# main.net
KiCad netlist of a schematic drawn in Altium Designer
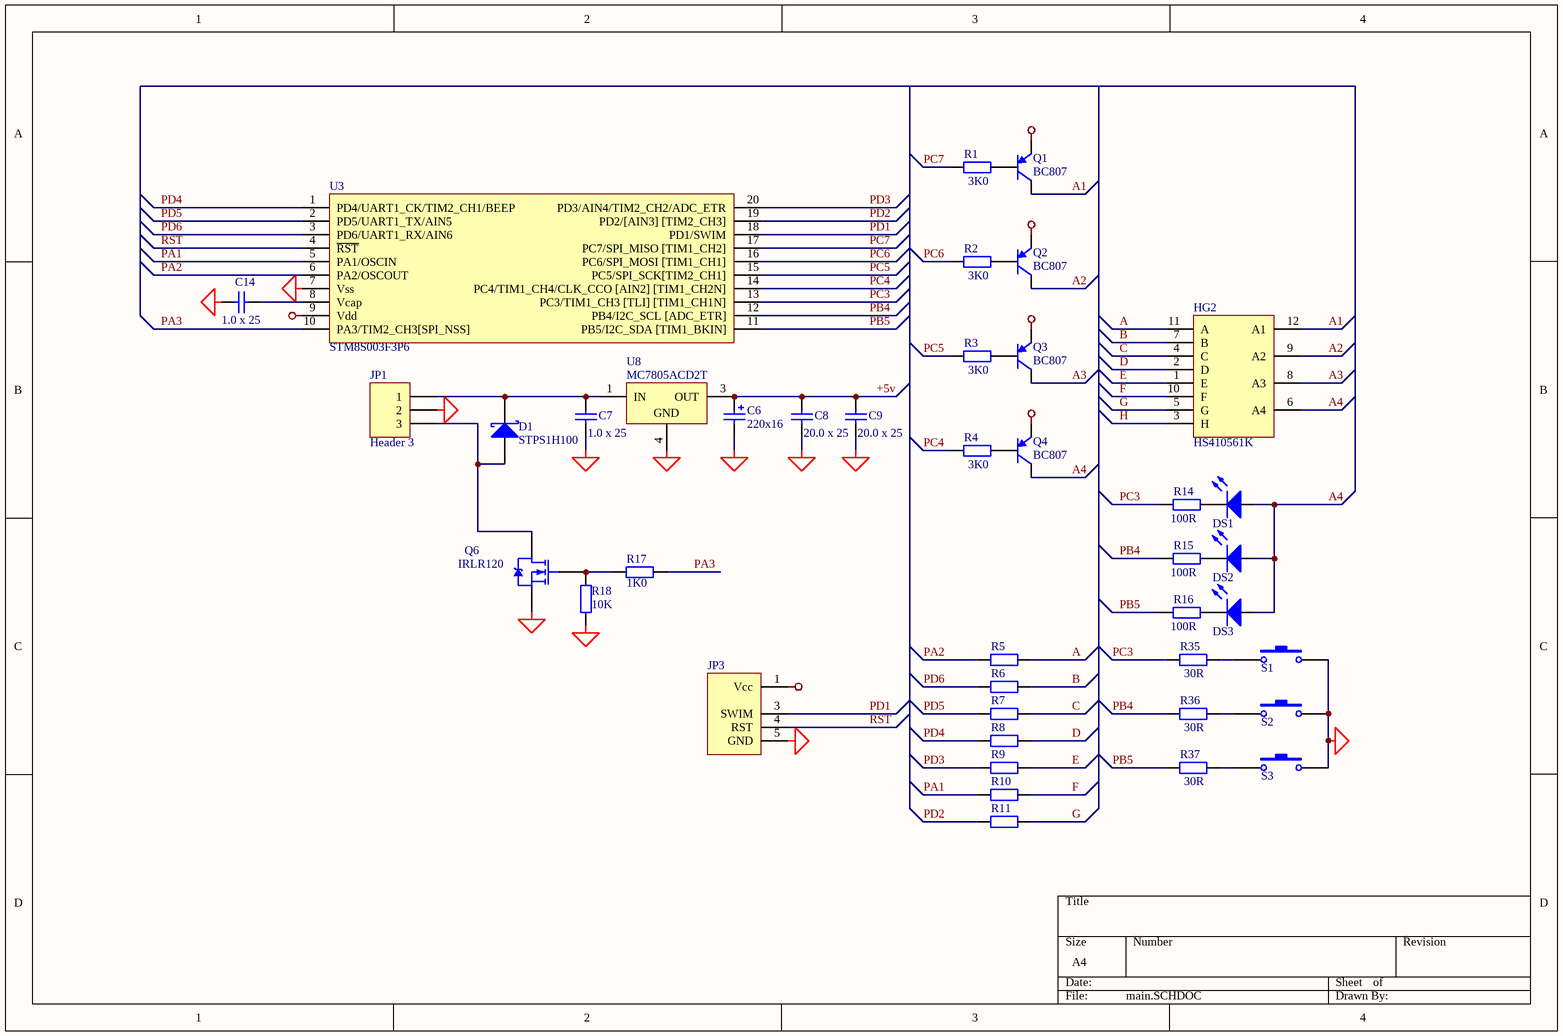
[diagram p0: main.SCHDOC]

(export (version "E")
  (design (tool "Eeschema 10.0.6"))
  (components
    (comp (ref "C6")
      (value "220x16")
      (footprint "el3")
      (description "Polarized Capacitor (Radial)")
      (fields (field (name "MANUFACTURER") "Generic Components") (field (name "PUBLISHER") "Altium Limited"))
      (libsource (lib "BUF") (part "Cap Pol"))
    )
    (comp (ref "C7")
      (value "1.0 x 25")
      (footprint "_1206")
      (description "Capacitor")
      (fields (field (name "MANUFACTURER") "Generic Components") (field (name "PUBLISHER") "Altium Limited"))
      (libsource (lib "BUF") (part "Cap"))
    )
    (comp (ref "C8")
      (value "20.0 x 25")
      (footprint "_1206")
      (description "Capacitor")
      (fields (field (name "MANUFACTURER") "Generic Components") (field (name "PUBLISHER") "Altium Limited"))
      (libsource (lib "BUF") (part "Cap"))
    )
    (comp (ref "C9")
      (value "20.0 x 25")
      (footprint "_1206")
      (description "Capacitor")
      (fields (field (name "MANUFACTURER") "Generic Components") (field (name "PUBLISHER") "Altium Limited"))
      (libsource (lib "BUF") (part "Cap"))
    )
    (comp (ref "C14")
      (value "1.0 x 25")
      (footprint "_1206")
      (description "Capacitor")
      (fields (field (name "MANUFACTURER") "Generic Components") (field (name "PUBLISHER") "Altium Limited"))
      (libsource (lib "Miscellaneous Devices") (part "Cap Semi"))
    )
    (comp (ref "D1")
      (value "STPS1H100")
      (footprint "DSO-C2/X2.3")
      (description "Schottky Rectifier")
      (fields
        (field (name "MANUFACTURER") "International Rectifier")
        (field (name "PUBLISHER") "Altium Limited")
      )
      (libsource (lib "IR Discrete Diode") (part "10BQ015"))
    )
    (comp (ref "DS1")
      (value "LED0")
      (footprint "el3")
      (description "Typical INFRARED GaAs LED")
      (fields (field (name "MANUFACTURER") "Generic Components") (field (name "PUBLISHER") "Altium Limited"))
      (libsource (lib "PAL") (part "LED0"))
    )
    (comp (ref "DS2")
      (value "LED0")
      (footprint "el3")
      (description "Typical INFRARED GaAs LED")
      (fields (field (name "MANUFACTURER") "Generic Components") (field (name "PUBLISHER") "Altium Limited"))
      (libsource (lib "PAL") (part "LED0"))
    )
    (comp (ref "DS3")
      (value "LED0")
      (footprint "el3")
      (description "Typical INFRARED GaAs LED")
      (fields (field (name "MANUFACTURER") "Generic Components") (field (name "PUBLISHER") "Altium Limited"))
      (libsource (lib "PAL") (part "LED0"))
    )
    (comp (ref "HG2") (value "HS410561K") (footprint "KEM-3461BS") (libsource (lib "PAL") (part "HS410561K")))
    (comp (ref "JP1")
      (value "Header 3")
      (footprint "BT5-3")
      (description "Header, 3-Pin")
      (fields (field (name "MANUFACTURER") "Generic Components") (field (name "PUBLISHER") "Altium Limited"))
      (libsource (lib "Miscellaneous Connectors") (part "Header 3"))
    )
    (comp (ref "JP3") (value "~") (footprint "HDR1X5_uart") (libsource (lib "PAL") (part "SWIM_CONN")))
    (comp (ref "Q1")
      (value "BC807")
      (footprint "SO-G3")
      (description "General Purpose Transistor PNP Silicon")
      (fields (field (name "MANUFACTURER") "Motorola") (field (name "PUBLISHER") "Altium Limited"))
      (libsource (lib "PAL") (part "BC857ALT1"))
    )
    (comp (ref "Q2")
      (value "BC807")
      (footprint "SO-G3")
      (description "General Purpose Transistor PNP Silicon")
      (fields (field (name "MANUFACTURER") "Motorola") (field (name "PUBLISHER") "Altium Limited"))
      (libsource (lib "PAL") (part "BC857ALT1"))
    )
    (comp (ref "Q3")
      (value "BC807")
      (footprint "SO-G3")
      (description "General Purpose Transistor PNP Silicon")
      (fields (field (name "MANUFACTURER") "Motorola") (field (name "PUBLISHER") "Altium Limited"))
      (libsource (lib "PAL") (part "BC857ALT1"))
    )
    (comp (ref "Q4")
      (value "BC807")
      (footprint "SO-G3")
      (description "General Purpose Transistor PNP Silicon")
      (fields (field (name "MANUFACTURER") "Motorola") (field (name "PUBLISHER") "Altium Limited"))
      (libsource (lib "PAL") (part "BC857ALT1"))
    )
    (comp (ref "Q6")
      (value "IRLR120")
      (footprint "SIP-G3/E8")
      (description "HEXFET N-Channel Power MOSFET")
      (fields
        (field (name "MANUFACTURER") "International Rectifier")
        (field (name "PUBLISHER") "Altium Limited")
      )
      (libsource (lib "IR Discrete MOSFET") (part "IRFR120"))
    )
    (comp (ref "R1")
      (value "3K0")
      (footprint "_1206")
      (description "Resistor")
      (fields (field (name "MANUFACTURER") "Generic Components") (field (name "PUBLISHER") "Altium Limited"))
      (libsource (lib "Miscellaneous Devices") (part "Res2"))
    )
    (comp (ref "R2")
      (value "3K0")
      (footprint "_1206")
      (description "Resistor")
      (fields (field (name "MANUFACTURER") "Generic Components") (field (name "PUBLISHER") "Altium Limited"))
      (libsource (lib "Miscellaneous Devices") (part "Res2"))
    )
    (comp (ref "R3")
      (value "3K0")
      (footprint "_1206")
      (description "Resistor")
      (fields (field (name "MANUFACTURER") "Generic Components") (field (name "PUBLISHER") "Altium Limited"))
      (libsource (lib "Miscellaneous Devices") (part "Res2"))
    )
    (comp (ref "R4")
      (value "3K0")
      (footprint "_1206")
      (description "Resistor")
      (fields (field (name "MANUFACTURER") "Generic Components") (field (name "PUBLISHER") "Altium Limited"))
      (libsource (lib "Miscellaneous Devices") (part "Res2"))
    )
    (comp (ref "R5")
      (value "100R")
      (footprint "_1206")
      (description "Resistor")
      (fields (field (name "MANUFACTURER") "Generic Components") (field (name "PUBLISHER") "Altium Limited"))
      (libsource (lib "Miscellaneous Devices") (part "Res2"))
    )
    (comp (ref "R6")
      (value "100R")
      (footprint "_1206")
      (description "Resistor")
      (fields (field (name "MANUFACTURER") "Generic Components") (field (name "PUBLISHER") "Altium Limited"))
      (libsource (lib "Miscellaneous Devices") (part "Res2"))
    )
    (comp (ref "R7")
      (value "100R")
      (footprint "_1206")
      (description "Resistor")
      (fields (field (name "MANUFACTURER") "Generic Components") (field (name "PUBLISHER") "Altium Limited"))
      (libsource (lib "Miscellaneous Devices") (part "Res2"))
    )
    (comp (ref "R8")
      (value "100R")
      (footprint "_1206")
      (description "Resistor")
      (fields (field (name "MANUFACTURER") "Generic Components") (field (name "PUBLISHER") "Altium Limited"))
      (libsource (lib "Miscellaneous Devices") (part "Res2"))
    )
    (comp (ref "R9")
      (value "100R")
      (footprint "_1206")
      (description "Resistor")
      (fields (field (name "MANUFACTURER") "Generic Components") (field (name "PUBLISHER") "Altium Limited"))
      (libsource (lib "Miscellaneous Devices") (part "Res2"))
    )
    (comp (ref "R10")
      (value "100R")
      (footprint "_1206")
      (description "Resistor")
      (fields (field (name "MANUFACTURER") "Generic Components") (field (name "PUBLISHER") "Altium Limited"))
      (libsource (lib "Miscellaneous Devices") (part "Res2"))
    )
    (comp (ref "R11")
      (value "100R")
      (footprint "_1206")
      (description "Resistor")
      (fields (field (name "MANUFACTURER") "Generic Components") (field (name "PUBLISHER") "Altium Limited"))
      (libsource (lib "Miscellaneous Devices") (part "Res2"))
    )
    (comp (ref "R14")
      (value "100R")
      (footprint "_1206")
      (description "Resistor")
      (fields (field (name "MANUFACTURER") "Generic Components") (field (name "PUBLISHER") "Altium Limited"))
      (libsource (lib "Miscellaneous Devices") (part "Res2"))
    )
    (comp (ref "R15")
      (value "100R")
      (footprint "_1206")
      (description "Resistor")
      (fields (field (name "MANUFACTURER") "Generic Components") (field (name "PUBLISHER") "Altium Limited"))
      (libsource (lib "Miscellaneous Devices") (part "Res2"))
    )
    (comp (ref "R16")
      (value "100R")
      (footprint "_1206")
      (description "Resistor")
      (fields (field (name "MANUFACTURER") "Generic Components") (field (name "PUBLISHER") "Altium Limited"))
      (libsource (lib "Miscellaneous Devices") (part "Res2"))
    )
    (comp (ref "R17")
      (value "1K0")
      (footprint "_1206")
      (description "Resistor")
      (fields (field (name "MANUFACTURER") "Generic Components") (field (name "PUBLISHER") "Altium Limited"))
      (libsource (lib "Miscellaneous Devices") (part "Res2"))
    )
    (comp (ref "R18")
      (value "10K")
      (footprint "_1206")
      (description "Resistor")
      (fields (field (name "MANUFACTURER") "Generic Components") (field (name "PUBLISHER") "Altium Limited"))
      (libsource (lib "") (part "Res2_1"))
    )
    (comp (ref "R35")
      (value "30R")
      (footprint "_1206")
      (description "Resistor")
      (fields (field (name "MANUFACTURER") "Generic Components") (field (name "PUBLISHER") "Altium Limited"))
      (libsource (lib "Miscellaneous Devices") (part "Res2"))
    )
    (comp (ref "R36")
      (value "30R")
      (footprint "_1206")
      (description "Resistor")
      (fields (field (name "MANUFACTURER") "Generic Components") (field (name "PUBLISHER") "Altium Limited"))
      (libsource (lib "Miscellaneous Devices") (part "Res2"))
    )
    (comp (ref "R37")
      (value "30R")
      (footprint "_1206")
      (description "Resistor")
      (fields (field (name "MANUFACTURER") "Generic Components") (field (name "PUBLISHER") "Altium Limited"))
      (libsource (lib "Miscellaneous Devices") (part "Res2"))
    )
    (comp (ref "S1")
      (value "SWT-6")
      (footprint "SWT-6")
      (description "Switch")
      (fields (field (name "MANUFACTURER") "Generic Components") (field (name "PUBLISHER") "Altium Limited"))
      (libsource (lib "PAL") (part "SWT-6"))
    )
    (comp (ref "S2")
      (value "SWT-6")
      (footprint "SWT-6")
      (description "Switch")
      (fields (field (name "MANUFACTURER") "Generic Components") (field (name "PUBLISHER") "Altium Limited"))
      (libsource (lib "PAL") (part "SWT-6"))
    )
    (comp (ref "S3")
      (value "SWT-6")
      (footprint "SWT-6")
      (description "Switch")
      (fields (field (name "MANUFACTURER") "Generic Components") (field (name "PUBLISHER") "Altium Limited"))
      (libsource (lib "PAL") (part "SWT-6"))
    )
    (comp (ref "U3") (value "~") (footprint "TSSO6x6-G20/Y1.6") (libsource (lib "PAL") (part "STM8S103F")))
    (comp (ref "U8")
      (value "MC7805ACD2T")
      (footprint "D2PAK")
      (description "Three-Terminal Positive Voltage Regulator")
      (fields (field (name "MANUFACTURER") "ON Semiconductor") (field (name "PUBLISHER") "Altium Limited"))
      (libsource (lib "ON Semi Power Mgt Voltage Regulator") (part "MC7805ACD2T"))
    )
  )
  (nets
    (net (code "1") (name "+5v") (class "Default")
      (node (ref "C6") (pin "1") (pinfunction "1_1") (pintype "passive"))
      (node (ref "C8") (pin "2") (pinfunction "2_2") (pintype "passive"))
      (node (ref "C9") (pin "2") (pinfunction "2_2") (pintype "passive"))
      (node (ref "JP3") (pin "1") (pinfunction "Vcc_1") (pintype "passive"))
      (node (ref "Q1") (pin "2") (pinfunction "E_2") (pintype "passive"))
      (node (ref "Q2") (pin "2") (pinfunction "E_2") (pintype "passive"))
      (node (ref "Q3") (pin "2") (pinfunction "E_2") (pintype "passive"))
      (node (ref "Q4") (pin "2") (pinfunction "E_2") (pintype "passive"))
      (node (ref "U3") (pin "9") (pinfunction "Vdd_9") (pintype "passive"))
      (node (ref "U8") (pin "3") (pinfunction "OUT_3") (pintype "power_in"))
    )
    (net (code "2") (name "/A") (class "Default")
      (node (ref "HG2") (pin "11") (pinfunction "A_11") (pintype "passive"))
      (node (ref "R5") (pin "1") (pinfunction "1_1") (pintype "passive"))
    )
    (net (code "3") (name "/A1") (class "Default")
      (node (ref "HG2") (pin "12") (pinfunction "A1_12") (pintype "passive"))
      (node (ref "Q1") (pin "3") (pinfunction "C_3") (pintype "passive"))
    )
    (net (code "4") (name "/A2") (class "Default")
      (node (ref "HG2") (pin "9") (pinfunction "A2_9") (pintype "passive"))
      (node (ref "Q2") (pin "3") (pinfunction "C_3") (pintype "passive"))
    )
    (net (code "5") (name "/A3") (class "Default")
      (node (ref "HG2") (pin "8") (pinfunction "A3_8") (pintype "passive"))
      (node (ref "Q3") (pin "3") (pinfunction "C_3") (pintype "passive"))
    )
    (net (code "6") (name "/A4") (class "Default")
      (node (ref "DS1") (pin "1") (pinfunction "A_1") (pintype "passive"))
      (node (ref "DS2") (pin "1") (pinfunction "A_1") (pintype "passive"))
      (node (ref "DS3") (pin "1") (pinfunction "A_1") (pintype "passive"))
      (node (ref "HG2") (pin "6") (pinfunction "A4_6") (pintype "passive"))
      (node (ref "Q4") (pin "3") (pinfunction "C_3") (pintype "passive"))
    )
    (net (code "7") (name "/B") (class "Default")
      (node (ref "HG2") (pin "7") (pinfunction "B_7") (pintype "passive"))
      (node (ref "R6") (pin "1") (pinfunction "1_1") (pintype "passive"))
    )
    (net (code "8") (name "/C") (class "Default")
      (node (ref "HG2") (pin "4") (pinfunction "C_4") (pintype "passive"))
      (node (ref "R7") (pin "1") (pinfunction "1_1") (pintype "passive"))
    )
    (net (code "9") (name "/D") (class "Default")
      (node (ref "HG2") (pin "2") (pinfunction "D_2") (pintype "passive"))
      (node (ref "R8") (pin "1") (pinfunction "1_1") (pintype "passive"))
    )
    (net (code "10") (name "/E") (class "Default")
      (node (ref "HG2") (pin "1") (pinfunction "E_1") (pintype "passive"))
      (node (ref "R9") (pin "1") (pinfunction "1_1") (pintype "passive"))
    )
    (net (code "11") (name "/F") (class "Default")
      (node (ref "HG2") (pin "10") (pinfunction "F_10") (pintype "passive"))
      (node (ref "R10") (pin "1") (pinfunction "1_1") (pintype "passive"))
    )
    (net (code "12") (name "/G") (class "Default")
      (node (ref "HG2") (pin "5") (pinfunction "G_5") (pintype "passive"))
      (node (ref "R11") (pin "1") (pinfunction "1_1") (pintype "passive"))
    )
    (net (code "13") (name "/H") (class "Default")
      (node (ref "HG2") (pin "3") (pinfunction "H_3") (pintype "passive"))
    )
    (net (code "14") (name "/PA1") (class "Default")
      (node (ref "R10") (pin "2") (pinfunction "2_2") (pintype "passive"))
      (node (ref "U3") (pin "5") (pinfunction "PA1/OSCIN_5") (pintype "passive"))
    )
    (net (code "15") (name "/PA2") (class "Default")
      (node (ref "R5") (pin "2") (pinfunction "2_2") (pintype "passive"))
      (node (ref "U3") (pin "6") (pinfunction "PA2/OSCOUT_6") (pintype "passive"))
    )
    (net (code "16") (name "/PA3") (class "Default")
      (node (ref "R17") (pin "1") (pinfunction "1_1") (pintype "passive"))
      (node (ref "U3") (pin "10") (pinfunction "PA3/TIM2_CH3[SPI_NSS]_10") (pintype "passive"))
    )
    (net (code "17") (name "/PB4") (class "Default")
      (node (ref "R15") (pin "2") (pinfunction "2_2") (pintype "passive"))
      (node (ref "R36") (pin "2") (pinfunction "2_2") (pintype "passive"))
      (node (ref "U3") (pin "12") (pinfunction "PB4/I2C_SCL_[ADC_ETR]_12") (pintype "passive"))
    )
    (net (code "18") (name "/PB5") (class "Default")
      (node (ref "R16") (pin "2") (pinfunction "2_2") (pintype "passive"))
      (node (ref "R37") (pin "2") (pinfunction "2_2") (pintype "passive"))
      (node (ref "U3") (pin "11") (pinfunction "PB5/I2C_SDA_[TIM1_BKIN]_11") (pintype "passive"))
    )
    (net (code "19") (name "/PC3") (class "Default")
      (node (ref "R14") (pin "2") (pinfunction "2_2") (pintype "passive"))
      (node (ref "R35") (pin "2") (pinfunction "2_2") (pintype "passive"))
      (node (ref "U3") (pin "13") (pinfunction "PC3/TIM1_CH3_[TLI]_[TIM1_CH1N]_13") (pintype "passive"))
    )
    (net (code "20") (name "/PC4") (class "Default")
      (node (ref "R4") (pin "2") (pinfunction "2_2") (pintype "passive"))
      (node (ref "U3") (pin "14") (pinfunction "PC4/TIM1_CH4/CLK_CCO_[AIN2]_[TIM1_CH2N]_14") (pintype "passive"))
    )
    (net (code "21") (name "/PC5") (class "Default")
      (node (ref "R3") (pin "2") (pinfunction "2_2") (pintype "passive"))
      (node (ref "U3") (pin "15") (pinfunction "PC5/SPI_SCK[TIM2_CH1]_15") (pintype "passive"))
    )
    (net (code "22") (name "/PC6") (class "Default")
      (node (ref "R2") (pin "2") (pinfunction "2_2") (pintype "passive"))
      (node (ref "U3") (pin "16") (pinfunction "PC6/SPI_MOSI_[TIM1_CH1]_16") (pintype "passive"))
    )
    (net (code "23") (name "/PC7") (class "Default")
      (node (ref "R1") (pin "2") (pinfunction "2_2") (pintype "passive"))
      (node (ref "U3") (pin "17") (pinfunction "PC7/SPI_MISO_[TIM1_CH2]_17") (pintype "passive"))
    )
    (net (code "24") (name "/PD1") (class "Default")
      (node (ref "JP3") (pin "3") (pinfunction "SWIM_3") (pintype "passive"))
      (node (ref "U3") (pin "18") (pinfunction "PD1/SWIM_18") (pintype "passive"))
    )
    (net (code "25") (name "/PD2") (class "Default")
      (node (ref "R11") (pin "2") (pinfunction "2_2") (pintype "passive"))
      (node (ref "U3") (pin "19") (pinfunction "PD2/[AIN3]_[TIM2_CH3]_19") (pintype "passive"))
    )
    (net (code "26") (name "/PD3") (class "Default")
      (node (ref "R9") (pin "2") (pinfunction "2_2") (pintype "passive"))
      (node (ref "U3") (pin "20") (pinfunction "PD3/AIN4/TIM2_CH2/ADC_ETR_20") (pintype "passive"))
    )
    (net (code "27") (name "/PD4") (class "Default")
      (node (ref "R8") (pin "2") (pinfunction "2_2") (pintype "passive"))
      (node (ref "U3") (pin "1") (pinfunction "PD4/UART1_CK/TIM2_CH1/BEEP_1") (pintype "passive"))
    )
    (net (code "28") (name "/PD5") (class "Default")
      (node (ref "R7") (pin "2") (pinfunction "2_2") (pintype "passive"))
      (node (ref "U3") (pin "2") (pinfunction "PD5/UART1_TX/AIN5_2") (pintype "passive"))
    )
    (net (code "29") (name "/PD6") (class "Default")
      (node (ref "R6") (pin "2") (pinfunction "2_2") (pintype "passive"))
      (node (ref "U3") (pin "3") (pinfunction "PD6/UART1_RX/AIN6_3") (pintype "passive"))
    )
    (net (code "30") (name "/RST") (class "Default")
      (node (ref "JP3") (pin "4") (pinfunction "RST_4") (pintype "passive"))
      (node (ref "U3") (pin "4") (pinfunction "~{RST}_4") (pintype "passive"))
    )
    (net (code "31") (name "GND") (class "Default")
      (node (ref "C14") (pin "1") (pinfunction "1_1") (pintype "passive"))
      (node (ref "C6") (pin "2") (pinfunction "2_2") (pintype "passive"))
      (node (ref "C7") (pin "1") (pinfunction "1_1") (pintype "passive"))
      (node (ref "C8") (pin "1") (pinfunction "1_1") (pintype "passive"))
      (node (ref "C9") (pin "1") (pinfunction "1_1") (pintype "passive"))
      (node (ref "JP1") (pin "2") (pinfunction "2_2") (pintype "passive"))
      (node (ref "JP3") (pin "5") (pinfunction "GND_5") (pintype "passive"))
      (node (ref "Q6") (pin "3") (pinfunction "S_3") (pintype "passive"))
      (node (ref "R18") (pin "2") (pinfunction "2_2") (pintype "passive"))
      (node (ref "S1") (pin "2") (pinfunction "2_2") (pintype "passive"))
      (node (ref "S2") (pin "2") (pinfunction "2_2") (pintype "passive"))
      (node (ref "S3") (pin "2") (pinfunction "2_2") (pintype "passive"))
      (node (ref "U3") (pin "7") (pinfunction "Vss_7") (pintype "passive"))
      (node (ref "U8") (pin "4") (pinfunction "GND_4") (pintype "power_in"))
    )
    (net (code "32") (name "Net-(D1-A)") (class "Default")
      (node (ref "D1") (pin "1") (pinfunction "A_1") (pintype "passive"))
      (node (ref "JP1") (pin "3") (pinfunction "3_3") (pintype "passive"))
      (node (ref "Q6") (pin "4") (pinfunction "D_4") (pintype "passive"))
    )
    (net (code "33") (name "Net-(D1-K)") (class "Default")
      (node (ref "C7") (pin "2") (pinfunction "2_2") (pintype "passive"))
      (node (ref "D1") (pin "2") (pinfunction "K_2") (pintype "passive"))
      (node (ref "JP1") (pin "1") (pinfunction "1_1") (pintype "passive"))
      (node (ref "U8") (pin "1") (pinfunction "IN_1") (pintype "power_in"))
    )
    (net (code "34") (name "Net-(DS1-K)") (class "Default")
      (node (ref "DS1") (pin "2") (pinfunction "K_2") (pintype "passive"))
      (node (ref "R14") (pin "1") (pinfunction "1_1") (pintype "passive"))
    )
    (net (code "35") (name "Net-(DS2-K)") (class "Default")
      (node (ref "DS2") (pin "2") (pinfunction "K_2") (pintype "passive"))
      (node (ref "R15") (pin "1") (pinfunction "1_1") (pintype "passive"))
    )
    (net (code "36") (name "Net-(DS3-K)") (class "Default")
      (node (ref "DS3") (pin "2") (pinfunction "K_2") (pintype "passive"))
      (node (ref "R16") (pin "1") (pinfunction "1_1") (pintype "passive"))
    )
    (net (code "37") (name "Net-(Q1-B)") (class "Default")
      (node (ref "Q1") (pin "1") (pinfunction "B_1") (pintype "passive"))
      (node (ref "R1") (pin "1") (pinfunction "1_1") (pintype "passive"))
    )
    (net (code "38") (name "Net-(Q2-B)") (class "Default")
      (node (ref "Q2") (pin "1") (pinfunction "B_1") (pintype "passive"))
      (node (ref "R2") (pin "1") (pinfunction "1_1") (pintype "passive"))
    )
    (net (code "39") (name "Net-(Q3-B)") (class "Default")
      (node (ref "Q3") (pin "1") (pinfunction "B_1") (pintype "passive"))
      (node (ref "R3") (pin "1") (pinfunction "1_1") (pintype "passive"))
    )
    (net (code "40") (name "Net-(Q4-B)") (class "Default")
      (node (ref "Q4") (pin "1") (pinfunction "B_1") (pintype "passive"))
      (node (ref "R4") (pin "1") (pinfunction "1_1") (pintype "passive"))
    )
    (net (code "41") (name "Net-(Q6-G)") (class "Default")
      (node (ref "Q6") (pin "1") (pinfunction "G_1") (pintype "passive"))
      (node (ref "R17") (pin "2") (pinfunction "2_2") (pintype "passive"))
      (node (ref "R18") (pin "1") (pinfunction "1_1") (pintype "passive"))
    )
    (net (code "42") (name "Net-(R35-Pad1)") (class "Default")
      (node (ref "R35") (pin "1") (pinfunction "1_1") (pintype "passive"))
      (node (ref "S1") (pin "1") (pinfunction "1_1") (pintype "passive"))
    )
    (net (code "43") (name "Net-(R36-Pad1)") (class "Default")
      (node (ref "R36") (pin "1") (pinfunction "1_1") (pintype "passive"))
      (node (ref "S2") (pin "1") (pinfunction "1_1") (pintype "passive"))
    )
    (net (code "44") (name "Net-(R37-Pad1)") (class "Default")
      (node (ref "R37") (pin "1") (pinfunction "1_1") (pintype "passive"))
      (node (ref "S3") (pin "1") (pinfunction "1_1") (pintype "passive"))
    )
    (net (code "45") (name "Net-(U3-Vcap)") (class "Default")
      (node (ref "C14") (pin "2") (pinfunction "2_2") (pintype "passive"))
      (node (ref "U3") (pin "8") (pinfunction "Vcap_8") (pintype "passive"))
    )
  )
)
